# LAm-v2.net
KiCad netlist of a schematic drawn in EAGLE
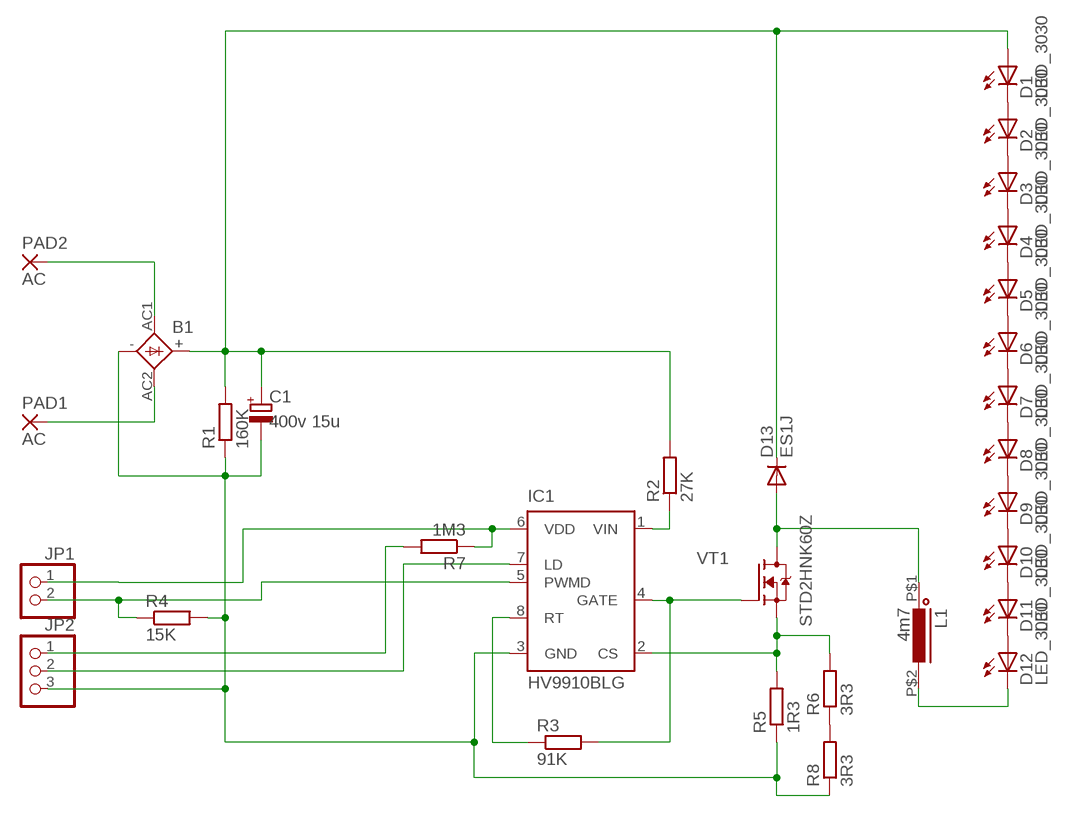
[diagram p0: schematic, sheet 1]

(export (version "E")
  (design (tool "Eeschema 10.0.6"))
  (components
    (comp (ref "B1")
      (value "BRIDGERB1A")
      (footprint "eagle-import:RB1A")
      (libsource (lib "eagle-import") (part "BRIDGERB1A"))
    )
    (comp (ref "C1")
      (value "400v 15u")
      (footprint "eagle-import:E5-13-35-HORIZ")
      (libsource (lib "eagle-import") (part "CAP-POL_E5-13-35-H"))
    )
    (comp (ref "D1")
      (value "LED_3030")
      (footprint "eagle-import:LED3030")
      (libsource (lib "eagle-import") (part "LED_3030"))
    )
    (comp (ref "D2")
      (value "LED_3030")
      (footprint "eagle-import:LED3030")
      (libsource (lib "eagle-import") (part "LED_3030"))
    )
    (comp (ref "D3")
      (value "LED_3030")
      (footprint "eagle-import:LED3030")
      (libsource (lib "eagle-import") (part "LED_3030"))
    )
    (comp (ref "D4")
      (value "LED_3030")
      (footprint "eagle-import:LED3030")
      (libsource (lib "eagle-import") (part "LED_3030"))
    )
    (comp (ref "D5")
      (value "LED_3030")
      (footprint "eagle-import:LED3030")
      (libsource (lib "eagle-import") (part "LED_3030"))
    )
    (comp (ref "D6")
      (value "LED_3030")
      (footprint "eagle-import:LED3030")
      (libsource (lib "eagle-import") (part "LED_3030"))
    )
    (comp (ref "D7")
      (value "LED_3030")
      (footprint "eagle-import:LED3030")
      (libsource (lib "eagle-import") (part "LED_3030"))
    )
    (comp (ref "D8")
      (value "LED_3030")
      (footprint "eagle-import:LED3030")
      (libsource (lib "eagle-import") (part "LED_3030"))
    )
    (comp (ref "D9")
      (value "LED_3030")
      (footprint "eagle-import:LED3030")
      (libsource (lib "eagle-import") (part "LED_3030"))
    )
    (comp (ref "D10")
      (value "LED_3030")
      (footprint "eagle-import:LED3030")
      (libsource (lib "eagle-import") (part "LED_3030"))
    )
    (comp (ref "D11")
      (value "LED_3030")
      (footprint "eagle-import:LED3030")
      (libsource (lib "eagle-import") (part "LED_3030"))
    )
    (comp (ref "D12")
      (value "LED_3030")
      (footprint "eagle-import:LED3030")
      (libsource (lib "eagle-import") (part "LED_3030"))
    )
    (comp (ref "D13")
      (value "ES1J")
      (footprint "eagle-import:DO214AC")
      (libsource (lib "eagle-import") (part "DIODE_ES1J"))
    )
    (comp (ref "IC1")
      (value "HV9910BLG")
      (footprint "eagle-import:SOIC-08LG")
      (fields (field (name "MPN") "MXHV9910B"))
      (libsource (lib "eagle-import") (part "HV9910BLG"))
    )
    (comp (ref "JP1")
      (value "PINHD-1X2/90")
      (footprint "eagle-import:1X02_90")
      (libsource (lib "eagle-import") (part "PINHD-1X2/90"))
    )
    (comp (ref "JP2")
      (value "PINHD-1X3/90")
      (footprint "eagle-import:1X03_90")
      (libsource (lib "eagle-import") (part "PINHD-1X3/90"))
    )
    (comp (ref "L1")
      (value "4m7")
      (footprint "eagle-import:SL1016")
      (libsource (lib "eagle-import") (part "INDUCTORSL1016"))
    )
    (comp (ref "PAD1")
      (value "AC")
      (footprint "eagle-import:3,81_1,4")
      (libsource (lib "eagle-import") (part "3,81/1,4"))
    )
    (comp (ref "PAD2")
      (value "AC")
      (footprint "eagle-import:3,81_1,4")
      (libsource (lib "eagle-import") (part "3,81/1,4"))
    )
    (comp (ref "R1")
      (value "160K")
      (footprint "eagle-import:MF-0125")
      (libsource (lib "eagle-import") (part "R_MF-0125"))
    )
    (comp (ref "R2")
      (value "27K")
      (footprint "eagle-import:MF-2")
      (libsource (lib "eagle-import") (part "R_MF-2"))
    )
    (comp (ref "R3")
      (value "91K")
      (footprint "eagle-import:R0805")
      (libsource (lib "eagle-import") (part "R_0805"))
    )
    (comp (ref "R4")
      (value "15K")
      (footprint "eagle-import:R0805")
      (libsource (lib "eagle-import") (part "R_0805"))
    )
    (comp (ref "R5")
      (value "1R3")
      (footprint "eagle-import:KNP-100B")
      (libsource (lib "eagle-import") (part "R_KNP-100B"))
    )
    (comp (ref "R6")
      (value "3R3")
      (footprint "eagle-import:R0805")
      (libsource (lib "eagle-import") (part "R_0805"))
    )
    (comp (ref "R7")
      (value "1M3")
      (footprint "eagle-import:R0805")
      (libsource (lib "eagle-import") (part "R_0805"))
    )
    (comp (ref "R8")
      (value "3R3")
      (footprint "eagle-import:R0805")
      (libsource (lib "eagle-import") (part "R_0805"))
    )
    (comp (ref "VT1")
      (value "STD2HNK60Z")
      (footprint "eagle-import:DPAK")
      (libsource (lib "eagle-import") (part "FET-NDPAK"))
    )
  )
  (nets
    (net (code "1") (name "Net-(D1-A)") (class "Default")
      (node (ref "B1") (pin "+") (pinfunction "+_+") (pintype "passive"))
      (node (ref "C1") (pin "+") (pinfunction "+_+") (pintype "passive"))
      (node (ref "D1") (pin "P$1") (pinfunction "A_P$1") (pintype "passive"))
      (node (ref "D13") (pin "C") (pinfunction "C_C") (pintype "passive"))
      (node (ref "R1") (pin "2") (pinfunction "2_2") (pintype "passive"))
      (node (ref "R2") (pin "2") (pinfunction "2_2") (pintype "passive"))
    )
    (net (code "2") (name "Net-(D1-C)") (class "Default")
      (node (ref "D1") (pin "P$2") (pinfunction "C_P$2") (pintype "passive"))
      (node (ref "D2") (pin "P$1") (pinfunction "A_P$1") (pintype "passive"))
    )
    (net (code "3") (name "Net-(D2-C)") (class "Default")
      (node (ref "D2") (pin "P$2") (pinfunction "C_P$2") (pintype "passive"))
      (node (ref "D3") (pin "P$1") (pinfunction "A_P$1") (pintype "passive"))
    )
    (net (code "4") (name "Net-(D3-C)") (class "Default")
      (node (ref "D3") (pin "P$2") (pinfunction "C_P$2") (pintype "passive"))
      (node (ref "D4") (pin "P$1") (pinfunction "A_P$1") (pintype "passive"))
    )
    (net (code "5") (name "Net-(D4-C)") (class "Default")
      (node (ref "D4") (pin "P$2") (pinfunction "C_P$2") (pintype "passive"))
      (node (ref "D5") (pin "P$1") (pinfunction "A_P$1") (pintype "passive"))
    )
    (net (code "6") (name "Net-(D5-C)") (class "Default")
      (node (ref "D5") (pin "P$2") (pinfunction "C_P$2") (pintype "passive"))
      (node (ref "D6") (pin "P$1") (pinfunction "A_P$1") (pintype "passive"))
    )
    (net (code "7") (name "Net-(D6-C)") (class "Default")
      (node (ref "D6") (pin "P$2") (pinfunction "C_P$2") (pintype "passive"))
      (node (ref "D7") (pin "P$1") (pinfunction "A_P$1") (pintype "passive"))
    )
    (net (code "8") (name "Net-(D7-C)") (class "Default")
      (node (ref "D7") (pin "P$2") (pinfunction "C_P$2") (pintype "passive"))
      (node (ref "D8") (pin "P$1") (pinfunction "A_P$1") (pintype "passive"))
    )
    (net (code "9") (name "Net-(D8-C)") (class "Default")
      (node (ref "D8") (pin "P$2") (pinfunction "C_P$2") (pintype "passive"))
      (node (ref "D9") (pin "P$1") (pinfunction "A_P$1") (pintype "passive"))
    )
    (net (code "10") (name "Net-(D10-A)") (class "Default")
      (node (ref "D10") (pin "P$1") (pinfunction "A_P$1") (pintype "passive"))
      (node (ref "D9") (pin "P$2") (pinfunction "C_P$2") (pintype "passive"))
    )
    (net (code "11") (name "Net-(D10-C)") (class "Default")
      (node (ref "D10") (pin "P$2") (pinfunction "C_P$2") (pintype "passive"))
      (node (ref "D11") (pin "P$1") (pinfunction "A_P$1") (pintype "passive"))
    )
    (net (code "12") (name "Net-(D11-C)") (class "Default")
      (node (ref "D11") (pin "P$2") (pinfunction "C_P$2") (pintype "passive"))
      (node (ref "D12") (pin "P$1") (pinfunction "A_P$1") (pintype "passive"))
    )
    (net (code "13") (name "Net-(D12-C)") (class "Default")
      (node (ref "D12") (pin "P$2") (pinfunction "C_P$2") (pintype "passive"))
      (node (ref "L1") (pin "P$2") (pinfunction "2_P$2") (pintype "passive"))
    )
    (net (code "14") (name "Net-(IC1-CS)") (class "Default")
      (node (ref "IC1") (pin "2") (pinfunction "CS_2") (pintype "input"))
      (node (ref "R5") (pin "2") (pinfunction "2_2") (pintype "passive"))
      (node (ref "R6") (pin "2") (pinfunction "2_2") (pintype "passive"))
      (node (ref "VT1") (pin "S") (pinfunction "S_S") (pintype "passive"))
    )
    (net (code "15") (name "Net-(IC1-GATE)") (class "Default")
      (node (ref "IC1") (pin "4") (pinfunction "GATE_4") (pintype "output"))
      (node (ref "R3") (pin "2") (pinfunction "2_2") (pintype "passive"))
      (node (ref "VT1") (pin "G") (pinfunction "G_G") (pintype "passive"))
    )
    (net (code "16") (name "Net-(IC1-GND)") (class "Default")
      (node (ref "B1") (pin "-") (pinfunction "-_-") (pintype "passive"))
      (node (ref "C1") (pin "-") (pinfunction "-_-") (pintype "passive"))
      (node (ref "IC1") (pin "3") (pinfunction "GND_3") (pintype "power_in"))
      (node (ref "JP2") (pin "3") (pinfunction "3_3") (pintype "passive"))
      (node (ref "R1") (pin "1") (pinfunction "1_1") (pintype "passive"))
      (node (ref "R4") (pin "2") (pinfunction "2_2") (pintype "passive"))
      (node (ref "R5") (pin "1") (pinfunction "1_1") (pintype "passive"))
      (node (ref "R8") (pin "1") (pinfunction "1_1") (pintype "passive"))
    )
    (net (code "17") (name "Net-(IC1-LD)") (class "Default")
      (node (ref "IC1") (pin "7") (pinfunction "LD_7") (pintype "input"))
      (node (ref "JP2") (pin "2") (pinfunction "2_2") (pintype "passive"))
    )
    (net (code "18") (name "Net-(IC1-PWMD)") (class "Default")
      (node (ref "IC1") (pin "5") (pinfunction "PWMD_5") (pintype "input"))
      (node (ref "JP1") (pin "2") (pinfunction "2_2") (pintype "passive"))
      (node (ref "R4") (pin "1") (pinfunction "1_1") (pintype "passive"))
    )
    (net (code "19") (name "Net-(IC1-RT)") (class "Default")
      (node (ref "IC1") (pin "8") (pinfunction "RT_8") (pintype "passive"))
      (node (ref "R3") (pin "1") (pinfunction "1_1") (pintype "passive"))
    )
    (net (code "20") (name "Net-(IC1-VDD)") (class "Default")
      (node (ref "IC1") (pin "6") (pinfunction "VDD_6") (pintype "power_in"))
      (node (ref "JP1") (pin "1") (pinfunction "1_1") (pintype "passive"))
      (node (ref "R7") (pin "1") (pinfunction "1_1") (pintype "passive"))
    )
    (net (code "21") (name "Net-(IC1-VIN)") (class "Default")
      (node (ref "IC1") (pin "1") (pinfunction "VIN_1") (pintype "input"))
      (node (ref "R2") (pin "1") (pinfunction "1_1") (pintype "passive"))
    )
    (net (code "22") (name "Net-(JP2-Pad1)") (class "Default")
      (node (ref "JP2") (pin "1") (pinfunction "1_1") (pintype "passive"))
      (node (ref "R7") (pin "2") (pinfunction "2_2") (pintype "passive"))
    )
    (net (code "23") (name "Net-(L1-1)") (class "Default")
      (node (ref "D13") (pin "A") (pinfunction "A_A") (pintype "passive"))
      (node (ref "L1") (pin "P$1") (pinfunction "1_P$1") (pintype "passive"))
      (node (ref "VT1") (pin "D") (pinfunction "D_D") (pintype "passive"))
    )
    (net (code "24") (name "Net-(PAD1-P)") (class "Default")
      (node (ref "B1") (pin "AC2") (pinfunction "AC2_AC2") (pintype "passive"))
      (node (ref "PAD1") (pin "1") (pinfunction "P_1") (pintype "passive"))
    )
    (net (code "25") (name "Net-(PAD2-P)") (class "Default")
      (node (ref "B1") (pin "AC1") (pinfunction "AC1_AC1") (pintype "passive"))
      (node (ref "PAD2") (pin "1") (pinfunction "P_1") (pintype "passive"))
    )
    (net (code "26") (name "Net-(R6-Pad1)") (class "Default")
      (node (ref "R6") (pin "1") (pinfunction "1_1") (pintype "passive"))
      (node (ref "R8") (pin "2") (pinfunction "2_2") (pintype "passive"))
    )
  )
)
